# ProPrj___2025-07-17.net
KiCad netlist of a schematic drawn in EasyEDA Pro
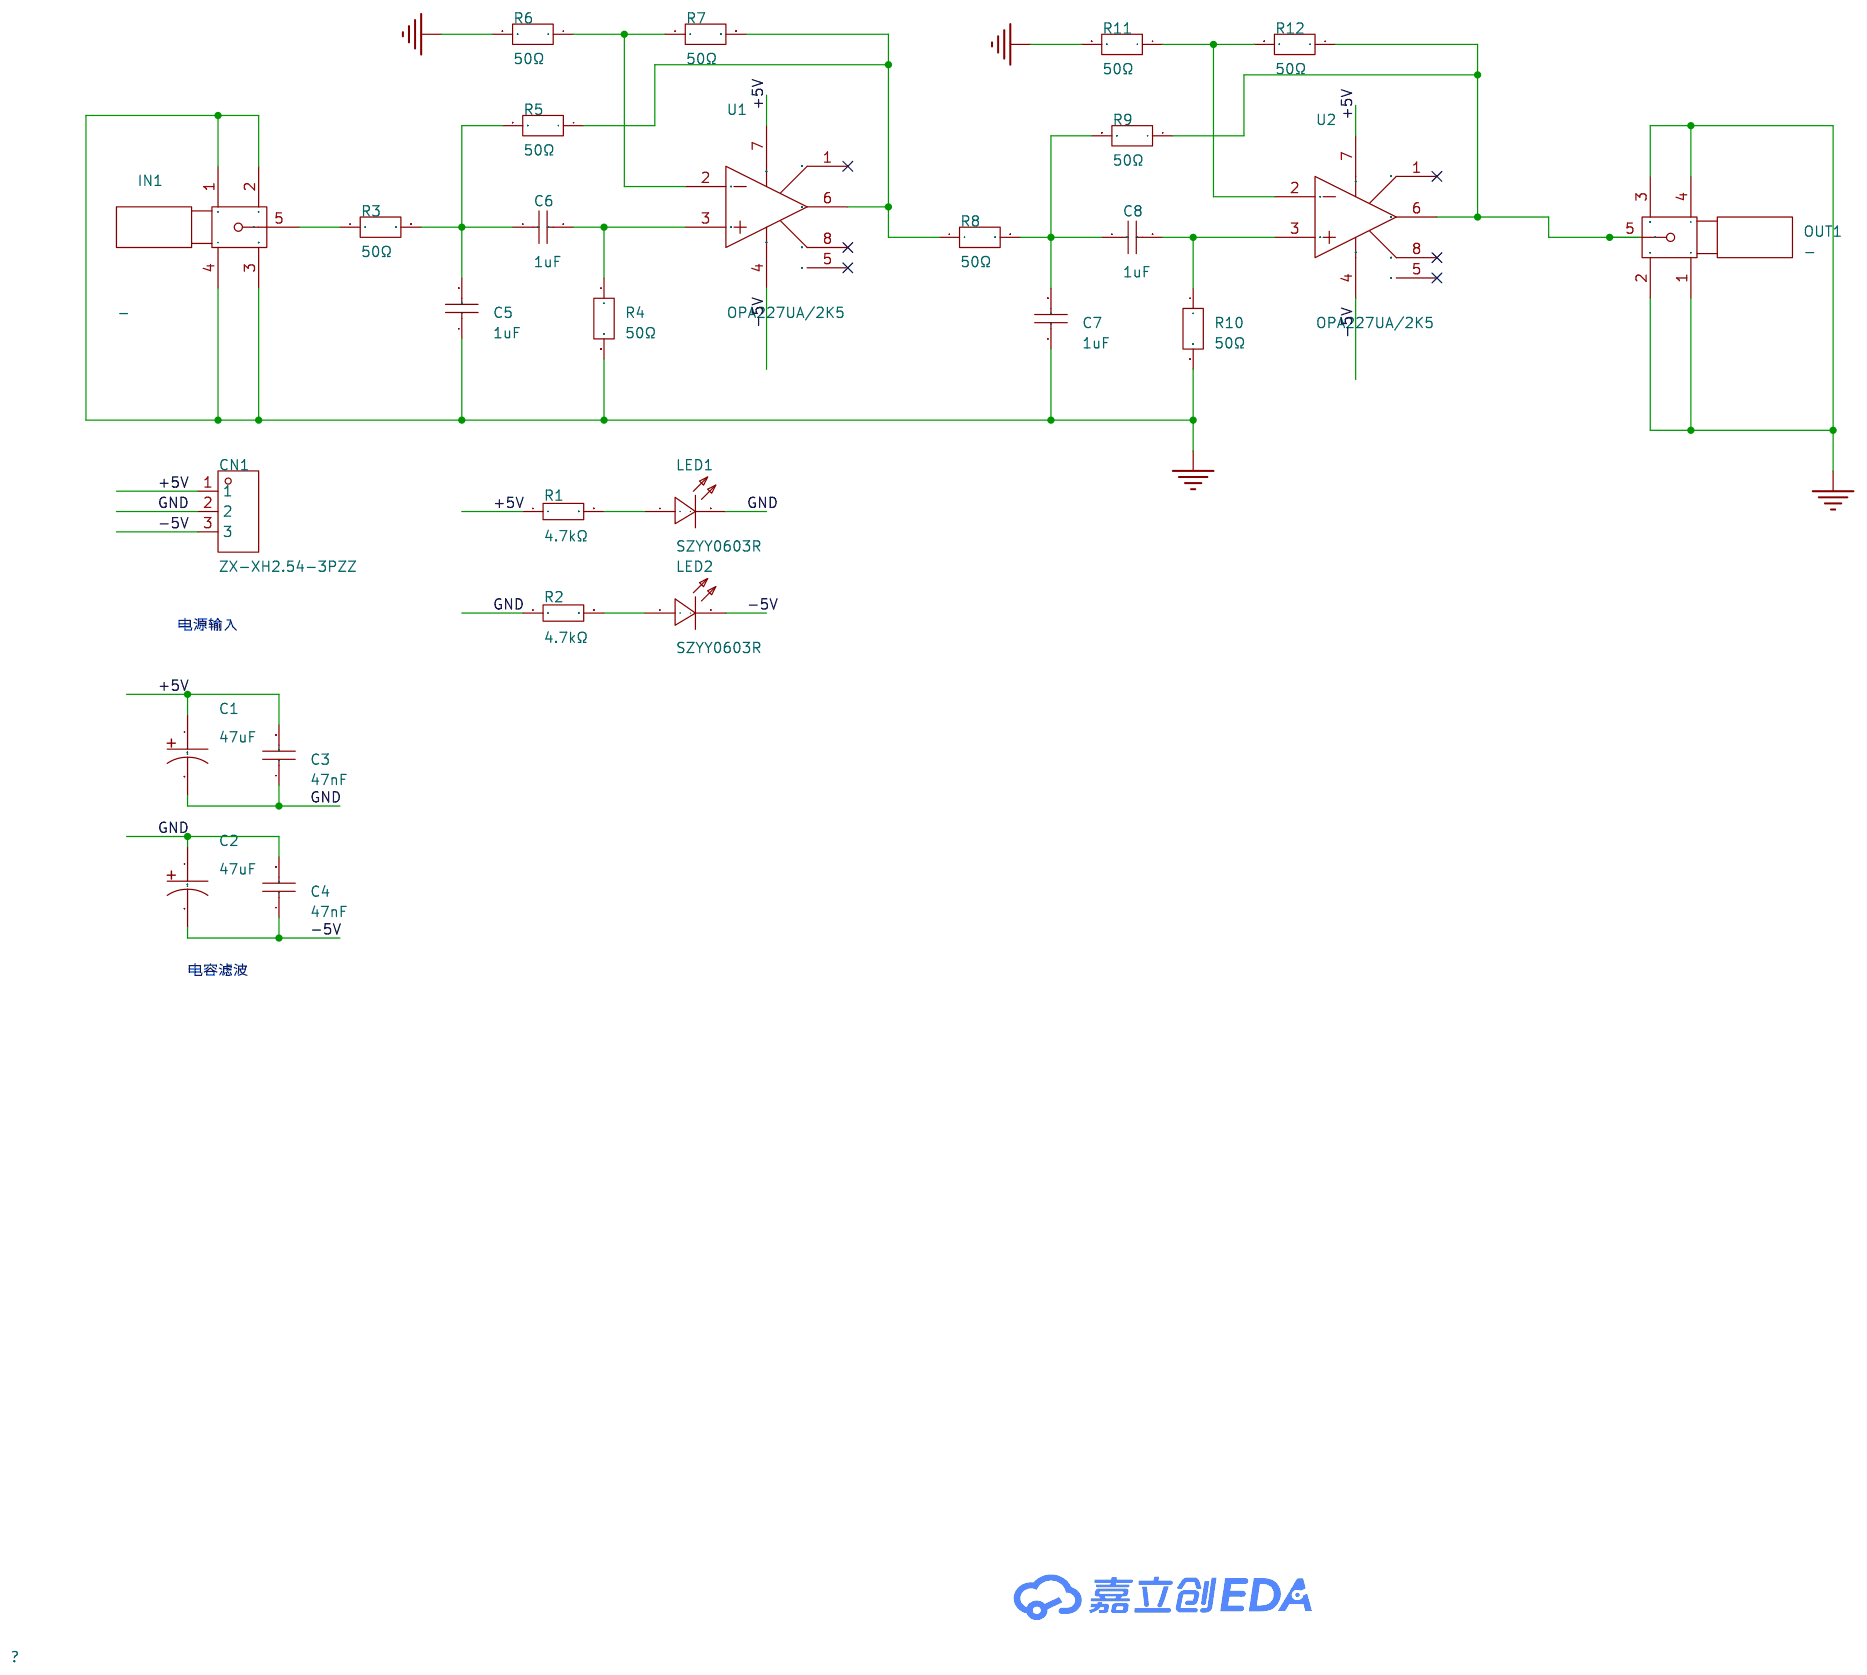
[diagram p0: schematic sheet]

(export (version "E")
  (design (tool "Eeschema 10.0.6"))
  (components
    (comp (ref "C1")
      (value "47uF")
      (footprint "easyedapro:CAP-TH_BD5.0-P2.00-D0.8-FD")
      (description "容值:47uF;精度:±20%;额定电压:25V;纹波电流:250mA@100kHz;等效串联电阻(ESR):300mΩ@100kHz;")
      (fields
        (field (name "Manufacturer Part") "NXB25V47M5*11 2.5TP")
        (field (name "Manufacturer") "SAMYOUNG(韩国三莹)")
      )
      (libsource (lib "easyedapro") (part "NXB25VB47M5*11_2.5TP"))
    )
    (comp (ref "C2")
      (value "47uF")
      (footprint "easyedapro:CAP-TH_BD5.0-P2.00-D0.8-FD")
      (description "容值:47uF;精度:±20%;额定电压:25V;纹波电流:250mA@100kHz;等效串联电阻(ESR):300mΩ@100kHz;")
      (fields
        (field (name "Manufacturer Part") "NXB25V47M5*11 2.5TP")
        (field (name "Manufacturer") "SAMYOUNG(韩国三莹)")
      )
      (libsource (lib "easyedapro") (part "NXB25VB47M5*11_2.5TP"))
    )
    (comp (ref "C3")
      (value "47nF")
      (footprint "easyedapro:C0805")
      (description "容值:47nF;精度:±10%;额定电压:50V;材质(温度系数):X7R;")
      (fields
        (field (name "Manufacturer Part") "CL21B473KBCNNNC")
        (field (name "Manufacturer") "SAMSUNG(三星)")
      )
      (libsource (lib "easyedapro") (part "CL21B473KBCNNNC"))
    )
    (comp (ref "C4")
      (value "47nF")
      (footprint "easyedapro:C0805")
      (description "容值:47nF;精度:±10%;额定电压:50V;材质(温度系数):X7R;")
      (fields
        (field (name "Manufacturer Part") "CL21B473KBCNNNC")
        (field (name "Manufacturer") "SAMSUNG(三星)")
      )
      (libsource (lib "easyedapro") (part "CL21B473KBCNNNC"))
    )
    (comp (ref "C5")
      (value "1uF")
      (footprint "easyedapro:C0805")
      (description "容值:1uF;精度:±10%;额定电压:50V;材质(温度系数):X7R;")
      (fields
        (field (name "Manufacturer Part") "CL21B105KBFNNNE")
        (field (name "Manufacturer") "SAMSUNG(三星)")
      )
      (libsource (lib "easyedapro") (part "CL21B105KBFNNNE"))
    )
    (comp (ref "C6")
      (value "1uF")
      (footprint "easyedapro:C0805")
      (description "容值:1uF;精度:±10%;额定电压:50V;材质(温度系数):X7R;")
      (fields
        (field (name "Manufacturer Part") "CL21B105KBFNNNE")
        (field (name "Manufacturer") "SAMSUNG(三星)")
      )
      (libsource (lib "easyedapro") (part "CL21B105KBFNNNE"))
    )
    (comp (ref "C7")
      (value "1uF")
      (footprint "easyedapro:C0805")
      (description "容值:1uF;精度:±10%;额定电压:50V;材质(温度系数):X7R;")
      (fields
        (field (name "Manufacturer Part") "CL21B105KBFNNNE")
        (field (name "Manufacturer") "SAMSUNG(三星)")
      )
      (libsource (lib "easyedapro") (part "CL21B105KBFNNNE"))
    )
    (comp (ref "C8")
      (value "1uF")
      (footprint "easyedapro:C0805")
      (description "容值:1uF;精度:±10%;额定电压:50V;材质(温度系数):X7R;")
      (fields
        (field (name "Manufacturer Part") "CL21B105KBFNNNE")
        (field (name "Manufacturer") "SAMSUNG(三星)")
      )
      (libsource (lib "easyedapro") (part "CL21B105KBFNNNE"))
    )
    (comp (ref "CN1")
      (value "ZX-XH2.54-3PZZ")
      (footprint "easyedapro:CONN-TH_3P-P2.54_2501S-3P")
      (fields (field (name "Manufacturer") "Megastar(兆星)"))
      (libsource (lib "easyedapro") (part "ZX-XH2.54-3PZZ"))
    )
    (comp (ref "IN1")
      (value "-")
      (footprint "easyedapro:SMA-SMD_BWSMA-KE-P001")
      (description "连接器类型:板端;接口类型:内孔;端口数量:1;接口直径:5.2mm;接口长度/高度:-;频率:-;射频系列:SMA;阻抗:50Ω;样式:偏脚;工作温度:-;")
      (fields
        (field (name "Manufacturer Part") "BWSMA-KE-P001")
        (field (name "Manufacturer") "BAT WIRELESS(蝙蝠无线)")
      )
      (libsource (lib "easyedapro") (part "BWSMA-KE-P001"))
    )
    (comp (ref "LED1")
      (value "SZYY0603R")
      (footprint "easyedapro:LED0603-R-RD")
      (fields (field (name "Manufacturer") "yongyu(永裕光电)"))
      (libsource (lib "easyedapro") (part "SZYY0603R"))
    )
    (comp (ref "LED2")
      (value "SZYY0603R")
      (footprint "easyedapro:LED0603-R-RD")
      (fields (field (name "Manufacturer") "yongyu(永裕光电)"))
      (libsource (lib "easyedapro") (part "SZYY0603R"))
    )
    (comp (ref "OUT1")
      (value "-")
      (footprint "easyedapro:SMA-SMD_BWSMA-KE-P001")
      (description "连接器类型:板端;接口类型:内孔;端口数量:1;接口直径:5.2mm;接口长度/高度:-;频率:-;射频系列:SMA;阻抗:50Ω;样式:偏脚;工作温度:-;")
      (fields
        (field (name "Manufacturer Part") "BWSMA-KE-P001")
        (field (name "Manufacturer") "BAT WIRELESS(蝙蝠无线)")
      )
      (libsource (lib "easyedapro") (part "BWSMA-KE-P001"))
    )
    (comp (ref "R1")
      (value "4.7kΩ")
      (footprint "easyedapro:R0805")
      (description "电阻类型:厚膜电阻;阻值:4.7kΩ;精度:±1%;功率:125mW;最大工作电压:150V;温度系数:±100ppm/°C;")
      (fields
        (field (name "Manufacturer Part") "0805W8F4701T5E")
        (field (name "Manufacturer") "UNI-ROYAL(厚声)")
      )
      (libsource (lib "easyedapro") (part "0805W8F4701T5E"))
    )
    (comp (ref "R2")
      (value "4.7kΩ")
      (footprint "easyedapro:R0805")
      (description "电阻类型:厚膜电阻;阻值:4.7kΩ;精度:±1%;功率:125mW;最大工作电压:150V;温度系数:±100ppm/°C;")
      (fields
        (field (name "Manufacturer Part") "0805W8F4701T5E")
        (field (name "Manufacturer") "UNI-ROYAL(厚声)")
      )
      (libsource (lib "easyedapro") (part "0805W8F4701T5E"))
    )
    (comp (ref "R3")
      (value "50Ω")
      (footprint "easyedapro:R0805")
      (description "电阻类型:薄膜电阻;阻值:50Ω;精度:±0.1%;功率:100mW;温度系数:±25ppm/°C;")
      (fields (field (name "Manufacturer Part") "TD05G50R0BT") (field (name "Manufacturer") "FH(风华)"))
      (libsource (lib "easyedapro") (part "TD05G50R0BT"))
    )
    (comp (ref "R4")
      (value "50Ω")
      (footprint "easyedapro:R0805")
      (description "电阻类型:薄膜电阻;阻值:50Ω;精度:±0.1%;功率:100mW;温度系数:±25ppm/°C;")
      (fields (field (name "Manufacturer Part") "TD05G50R0BT") (field (name "Manufacturer") "FH(风华)"))
      (libsource (lib "easyedapro") (part "TD05G50R0BT"))
    )
    (comp (ref "R5")
      (value "50Ω")
      (footprint "easyedapro:R0805")
      (description "电阻类型:薄膜电阻;阻值:50Ω;精度:±0.1%;功率:100mW;温度系数:±25ppm/°C;")
      (fields (field (name "Manufacturer Part") "TD05G50R0BT") (field (name "Manufacturer") "FH(风华)"))
      (libsource (lib "easyedapro") (part "TD05G50R0BT"))
    )
    (comp (ref "R6")
      (value "50Ω")
      (footprint "easyedapro:R0805")
      (description "电阻类型:薄膜电阻;阻值:50Ω;精度:±0.1%;功率:100mW;温度系数:±25ppm/°C;")
      (fields (field (name "Manufacturer Part") "TD05G50R0BT") (field (name "Manufacturer") "FH(风华)"))
      (libsource (lib "easyedapro") (part "TD05G50R0BT"))
    )
    (comp (ref "R7")
      (value "50Ω")
      (footprint "easyedapro:R0805")
      (description "电阻类型:薄膜电阻;阻值:50Ω;精度:±0.1%;功率:100mW;温度系数:±25ppm/°C;")
      (fields (field (name "Manufacturer Part") "TD05G50R0BT") (field (name "Manufacturer") "FH(风华)"))
      (libsource (lib "easyedapro") (part "TD05G50R0BT"))
    )
    (comp (ref "R8")
      (value "50Ω")
      (footprint "easyedapro:R0805")
      (description "电阻类型:薄膜电阻;阻值:50Ω;精度:±0.1%;功率:100mW;温度系数:±25ppm/°C;")
      (fields (field (name "Manufacturer Part") "TD05G50R0BT") (field (name "Manufacturer") "FH(风华)"))
      (libsource (lib "easyedapro") (part "TD05G50R0BT"))
    )
    (comp (ref "R9")
      (value "50Ω")
      (footprint "easyedapro:R0805")
      (description "电阻类型:薄膜电阻;阻值:50Ω;精度:±0.1%;功率:100mW;温度系数:±25ppm/°C;")
      (fields (field (name "Manufacturer Part") "TD05G50R0BT") (field (name "Manufacturer") "FH(风华)"))
      (libsource (lib "easyedapro") (part "TD05G50R0BT"))
    )
    (comp (ref "R10")
      (value "50Ω")
      (footprint "easyedapro:R0805")
      (description "电阻类型:薄膜电阻;阻值:50Ω;精度:±0.1%;功率:100mW;温度系数:±25ppm/°C;")
      (fields (field (name "Manufacturer Part") "TD05G50R0BT") (field (name "Manufacturer") "FH(风华)"))
      (libsource (lib "easyedapro") (part "TD05G50R0BT"))
    )
    (comp (ref "R11")
      (value "50Ω")
      (footprint "easyedapro:R0805")
      (description "电阻类型:薄膜电阻;阻值:50Ω;精度:±0.1%;功率:100mW;温度系数:±25ppm/°C;")
      (fields (field (name "Manufacturer Part") "TD05G50R0BT") (field (name "Manufacturer") "FH(风华)"))
      (libsource (lib "easyedapro") (part "TD05G50R0BT"))
    )
    (comp (ref "R12")
      (value "50Ω")
      (footprint "easyedapro:R0805")
      (description "电阻类型:薄膜电阻;阻值:50Ω;精度:±0.1%;功率:100mW;温度系数:±25ppm/°C;")
      (fields (field (name "Manufacturer Part") "TD05G50R0BT") (field (name "Manufacturer") "FH(风华)"))
      (libsource (lib "easyedapro") (part "TD05G50R0BT"))
    )
    (comp (ref "U1")
      (value "OPA227UA/2K5")
      (footprint "easyedapro:SOIC-8_L4.9-W3.9-P1.27-LS6.0-BL")
      (description "放大器数:单路;增益带宽积(GBP):8MHz;输入偏置电流(Ib):2.5nA;压摆率(SR):2.3V/us;轨到轨:-;")
      (fields (field (name "Manufacturer") "TI(德州仪器)"))
      (libsource (lib "easyedapro") (part "OPA227UA/2K5"))
    )
    (comp (ref "U2")
      (value "OPA227UA/2K5")
      (footprint "easyedapro:SOIC-8_L4.9-W3.9-P1.27-LS6.0-BL")
      (description "放大器数:单路;增益带宽积(GBP):8MHz;输入偏置电流(Ib):2.5nA;压摆率(SR):2.3V/us;轨到轨:-;")
      (fields (field (name "Manufacturer") "TI(德州仪器)"))
      (libsource (lib "easyedapro") (part "OPA227UA/2K5"))
    )
  )
  (nets
    (net (code "1") (name "/+5V") (class "Default")
      (node (ref "C1") (pin "1") (pinfunction "1_1") (pintype "unspecified"))
      (node (ref "C3") (pin "2") (pinfunction "2_2") (pintype "input"))
      (node (ref "CN1") (pin "1") (pinfunction "1_1") (pintype "unspecified"))
      (node (ref "R1") (pin "1") (pinfunction "1_1") (pintype "input"))
      (node (ref "U1") (pin "7") (pinfunction "VCC_7") (pintype "unspecified"))
      (node (ref "U2") (pin "7") (pinfunction "VCC_7") (pintype "unspecified"))
    )
    (net (code "2") (name "/-5V") (class "Default")
      (node (ref "C2") (pin "2") (pinfunction "2_2") (pintype "unspecified"))
      (node (ref "C4") (pin "1") (pinfunction "1_1") (pintype "input"))
      (node (ref "CN1") (pin "3") (pinfunction "3_3") (pintype "unspecified"))
      (node (ref "LED2") (pin "2") (pinfunction "-_2") (pintype "unspecified"))
      (node (ref "U1") (pin "4") (pinfunction "VSS_4") (pintype "unspecified"))
      (node (ref "U2") (pin "4") (pinfunction "VSS_4") (pintype "unspecified"))
    )
    (net (code "3") (name "GND") (class "Default")
      (node (ref "C1") (pin "2") (pinfunction "2_2") (pintype "unspecified"))
      (node (ref "C2") (pin "1") (pinfunction "1_1") (pintype "unspecified"))
      (node (ref "C3") (pin "1") (pinfunction "1_1") (pintype "input"))
      (node (ref "C4") (pin "2") (pinfunction "2_2") (pintype "input"))
      (node (ref "C5") (pin "1") (pinfunction "1_1") (pintype "input"))
      (node (ref "C7") (pin "1") (pinfunction "1_1") (pintype "input"))
      (node (ref "CN1") (pin "2") (pinfunction "2_2") (pintype "unspecified"))
      (node (ref "IN1") (pin "1") (pinfunction "1_1") (pintype "unspecified"))
      (node (ref "IN1") (pin "2") (pinfunction "2_2") (pintype "unspecified"))
      (node (ref "IN1") (pin "3") (pinfunction "3_3") (pintype "unspecified"))
      (node (ref "IN1") (pin "4") (pinfunction "4_4") (pintype "unspecified"))
      (node (ref "LED1") (pin "2") (pinfunction "-_2") (pintype "unspecified"))
      (node (ref "OUT1") (pin "1") (pinfunction "1_1") (pintype "unspecified"))
      (node (ref "OUT1") (pin "2") (pinfunction "2_2") (pintype "unspecified"))
      (node (ref "OUT1") (pin "3") (pinfunction "3_3") (pintype "unspecified"))
      (node (ref "OUT1") (pin "4") (pinfunction "4_4") (pintype "unspecified"))
      (node (ref "R10") (pin "2") (pinfunction "2_2") (pintype "unspecified"))
      (node (ref "R11") (pin "2") (pinfunction "2_2") (pintype "unspecified"))
      (node (ref "R2") (pin "1") (pinfunction "1_1") (pintype "input"))
      (node (ref "R4") (pin "2") (pinfunction "2_2") (pintype "unspecified"))
      (node (ref "R6") (pin "2") (pinfunction "2_2") (pintype "unspecified"))
    )
    (net (code "4") (name "Net-(C5-Pad2)") (class "Default")
      (node (ref "C5") (pin "2") (pinfunction "2_2") (pintype "input"))
      (node (ref "C6") (pin "1") (pinfunction "1_1") (pintype "input"))
      (node (ref "R3") (pin "2") (pinfunction "2_2") (pintype "unspecified"))
      (node (ref "R5") (pin "2") (pinfunction "2_2") (pintype "unspecified"))
    )
    (net (code "5") (name "Net-(C7-Pad2)") (class "Default")
      (node (ref "C7") (pin "2") (pinfunction "2_2") (pintype "input"))
      (node (ref "C8") (pin "1") (pinfunction "1_1") (pintype "input"))
      (node (ref "R8") (pin "2") (pinfunction "2_2") (pintype "unspecified"))
      (node (ref "R9") (pin "2") (pinfunction "2_2") (pintype "unspecified"))
    )
    (net (code "6") (name "Net-(IN1-Pad5)") (class "Default")
      (node (ref "IN1") (pin "5") (pinfunction "5_5") (pintype "unspecified"))
      (node (ref "R3") (pin "1") (pinfunction "1_1") (pintype "unspecified"))
    )
    (net (code "7") (name "Net-(LED1-+)") (class "Default")
      (node (ref "LED1") (pin "1") (pinfunction "+_1") (pintype "unspecified"))
      (node (ref "R1") (pin "2") (pinfunction "2_2") (pintype "input"))
    )
    (net (code "8") (name "Net-(LED2-+)") (class "Default")
      (node (ref "LED2") (pin "1") (pinfunction "+_1") (pintype "unspecified"))
      (node (ref "R2") (pin "2") (pinfunction "2_2") (pintype "input"))
    )
    (net (code "9") (name "Net-(U1-OUT)") (class "Default")
      (node (ref "R5") (pin "1") (pinfunction "1_1") (pintype "unspecified"))
      (node (ref "R7") (pin "2") (pinfunction "2_2") (pintype "unspecified"))
      (node (ref "R8") (pin "1") (pinfunction "1_1") (pintype "unspecified"))
      (node (ref "U1") (pin "6") (pinfunction "OUT_6") (pintype "output"))
    )
    (net (code "10") (name "Net-(U1-VIN+)") (class "Default")
      (node (ref "C6") (pin "2") (pinfunction "2_2") (pintype "input"))
      (node (ref "R4") (pin "1") (pinfunction "1_1") (pintype "unspecified"))
      (node (ref "U1") (pin "3") (pinfunction "VIN+_3") (pintype "unspecified"))
    )
    (net (code "11") (name "Net-(U1-VIN-)") (class "Default")
      (node (ref "R6") (pin "1") (pinfunction "1_1") (pintype "unspecified"))
      (node (ref "R7") (pin "1") (pinfunction "1_1") (pintype "unspecified"))
      (node (ref "U1") (pin "2") (pinfunction "VIN-_2") (pintype "unspecified"))
    )
    (net (code "12") (name "Net-(U2-OUT)") (class "Default")
      (node (ref "OUT1") (pin "5") (pinfunction "5_5") (pintype "unspecified"))
      (node (ref "R12") (pin "1") (pinfunction "1_1") (pintype "unspecified"))
      (node (ref "R9") (pin "1") (pinfunction "1_1") (pintype "unspecified"))
      (node (ref "U2") (pin "6") (pinfunction "OUT_6") (pintype "output"))
    )
    (net (code "13") (name "Net-(U2-VIN+)") (class "Default")
      (node (ref "C8") (pin "2") (pinfunction "2_2") (pintype "input"))
      (node (ref "R10") (pin "1") (pinfunction "1_1") (pintype "unspecified"))
      (node (ref "U2") (pin "3") (pinfunction "VIN+_3") (pintype "unspecified"))
    )
    (net (code "14") (name "Net-(U2-VIN-)") (class "Default")
      (node (ref "R11") (pin "1") (pinfunction "1_1") (pintype "unspecified"))
      (node (ref "R12") (pin "2") (pinfunction "2_2") (pintype "unspecified"))
      (node (ref "U2") (pin "2") (pinfunction "VIN-_2") (pintype "unspecified"))
    )
    (net (code "15") (name "unconnected-(U1-NC-Pad5)") (class "Default")
      (node (ref "U1") (pin "5") (pinfunction "NC_5") (pintype "unspecified+no_connect"))
    )
    (net (code "16") (name "unconnected-(U1-TRIM-Pad1)") (class "Default")
      (node (ref "U1") (pin "1") (pinfunction "TRIM_1") (pintype "unspecified+no_connect"))
    )
    (net (code "17") (name "unconnected-(U1-TRIM-Pad8)") (class "Default")
      (node (ref "U1") (pin "8") (pinfunction "TRIM_8") (pintype "unspecified+no_connect"))
    )
    (net (code "18") (name "unconnected-(U2-NC-Pad5)") (class "Default")
      (node (ref "U2") (pin "5") (pinfunction "NC_5") (pintype "unspecified+no_connect"))
    )
    (net (code "19") (name "unconnected-(U2-TRIM-Pad1)") (class "Default")
      (node (ref "U2") (pin "1") (pinfunction "TRIM_1") (pintype "unspecified+no_connect"))
    )
    (net (code "20") (name "unconnected-(U2-TRIM-Pad8)") (class "Default")
      (node (ref "U2") (pin "8") (pinfunction "TRIM_8") (pintype "unspecified+no_connect"))
    )
  )
)
